# MGB-001-IO.net
KiCad netlist of a schematic drawn in EAGLE
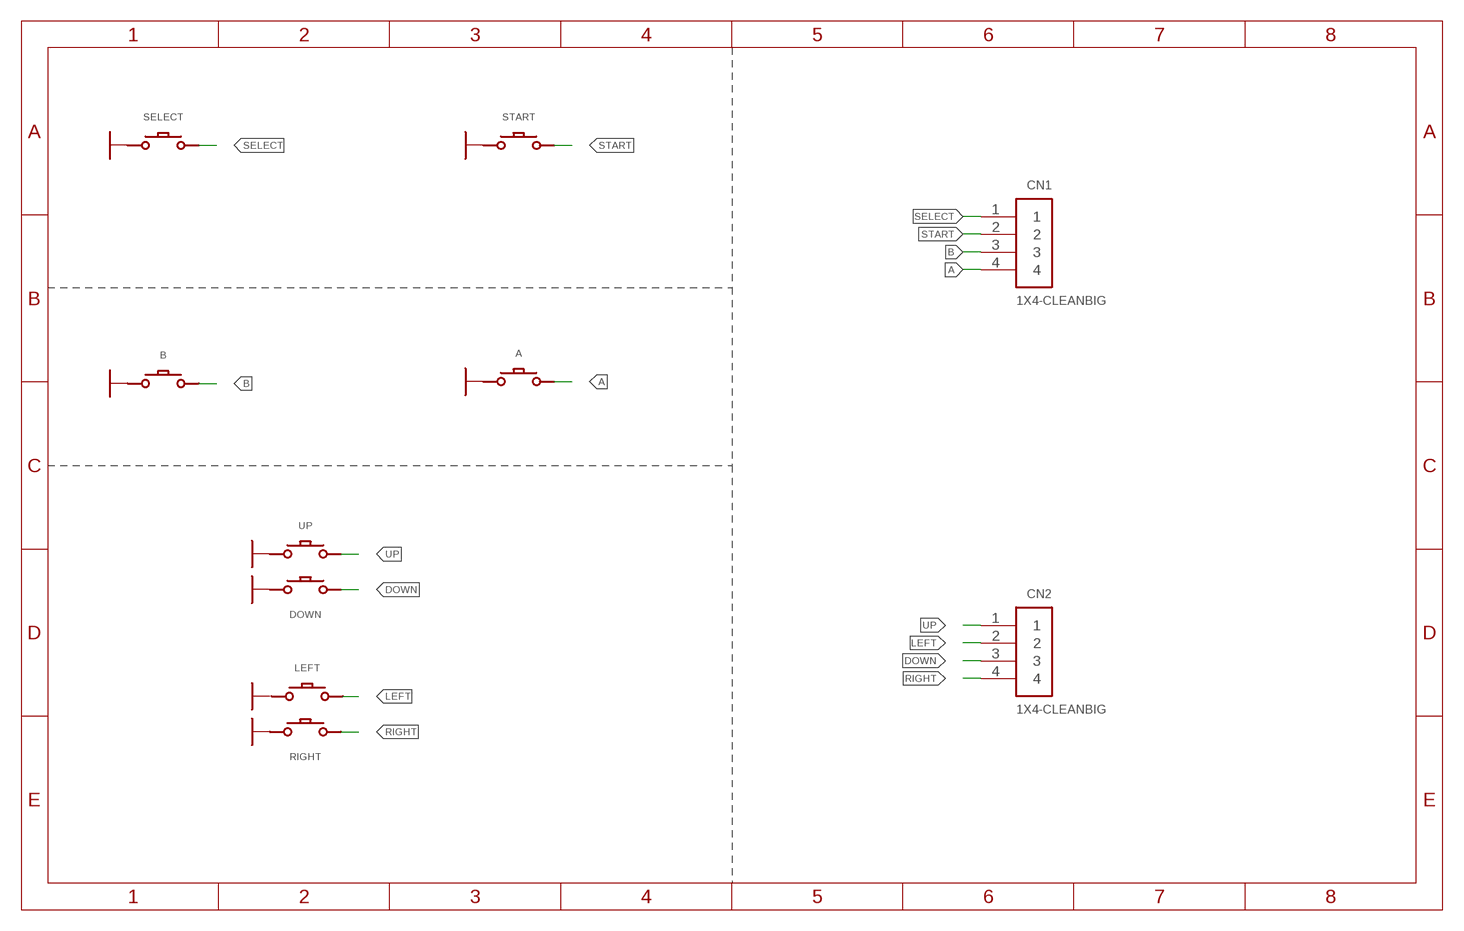
[diagram p0: schematic, sheet 1]
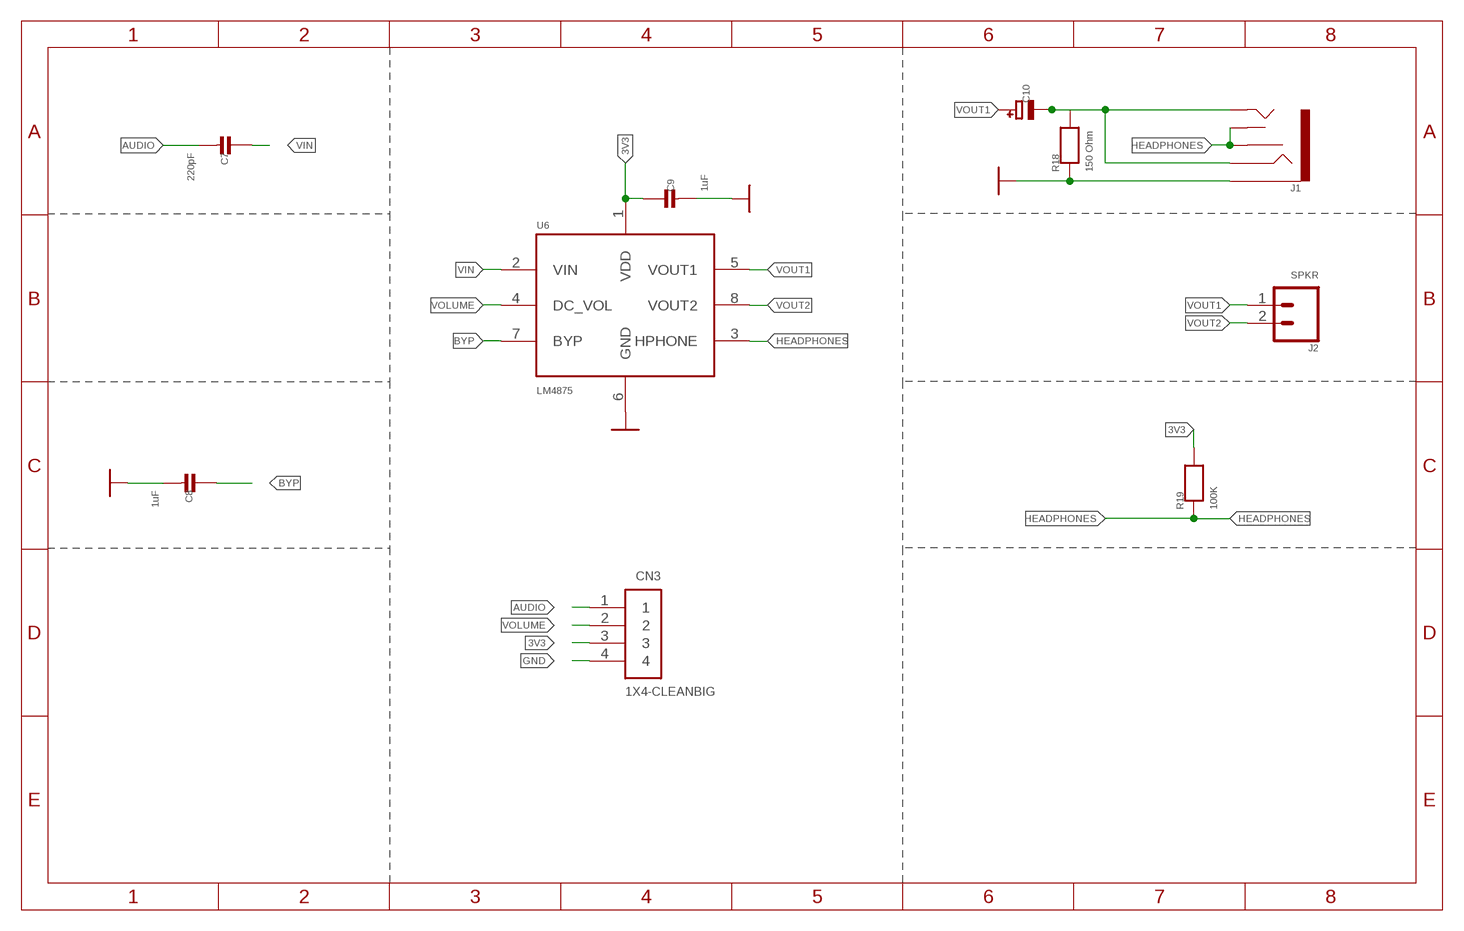
[diagram p1: schematic, sheet 2]
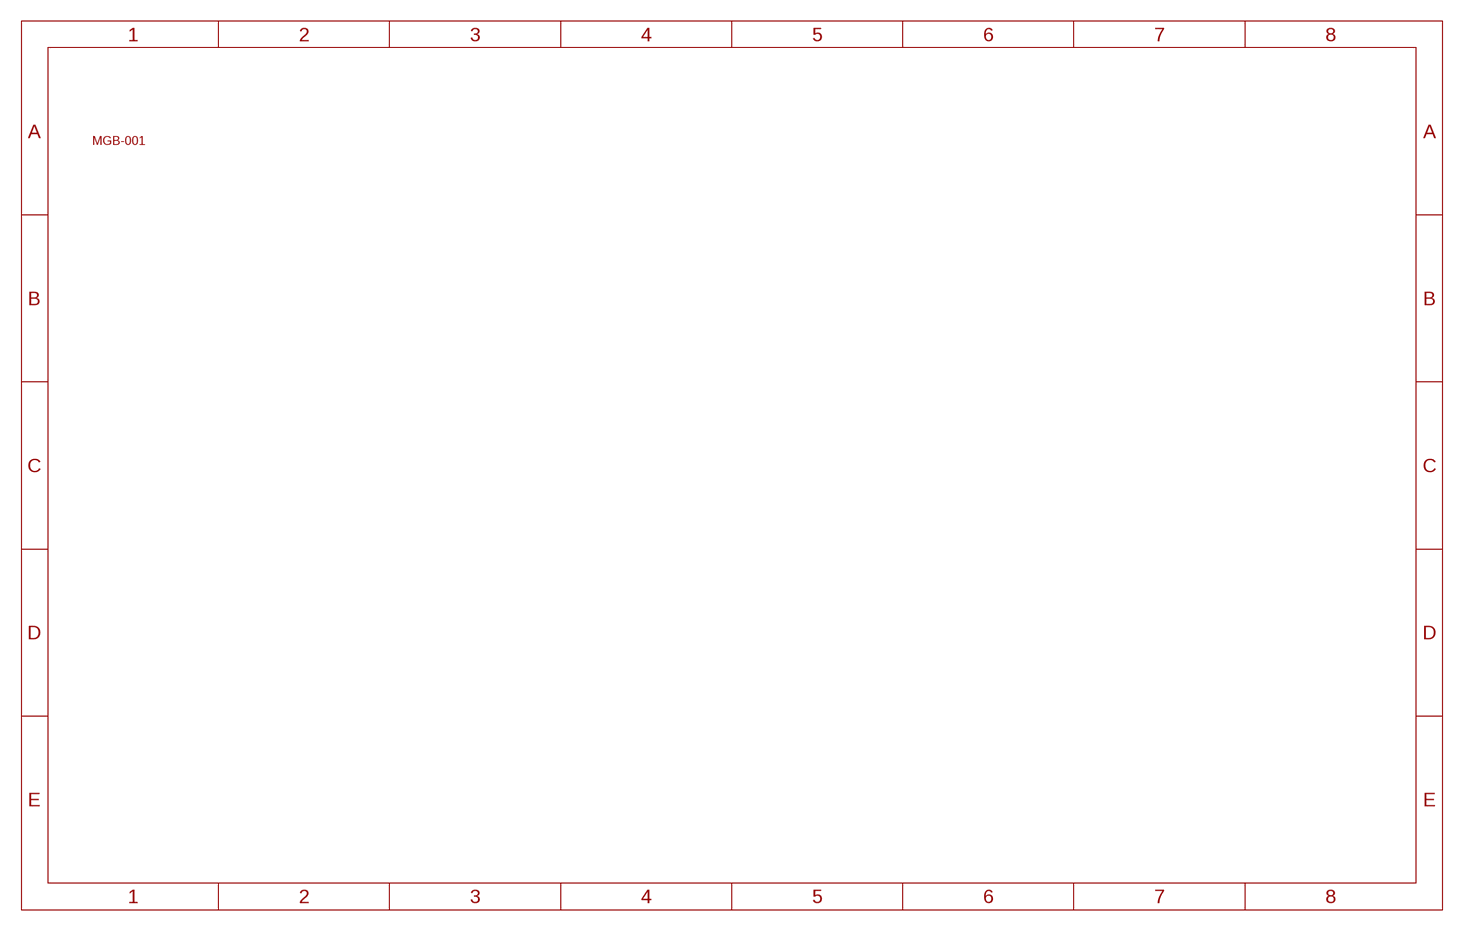
[diagram p2: schematic, sheet 3]

(export (version "E")
  (design (tool "Eeschema 10.0.6"))
  (components
    (comp (ref "C7")
      (value "220pF")
      (footprint "eagle-import:0603-MINI-CAP")
      (fields (field (name "MPN") "CL10C221JB8NNNC"))
      (libsource (lib "eagle-import") (part "CAP_CERAMIC"))
    )
    (comp (ref "C8")
      (value "1uF")
      (footprint "eagle-import:0603-MINI-CAP")
      (fields (field (name "MPN") "CL10A105KP8NNNC"))
      (libsource (lib "eagle-import") (part "CAP_CERAMIC"))
    )
    (comp (ref "C9")
      (value "1uF")
      (footprint "eagle-import:0603-MINI-CAP")
      (fields (field (name "MPN") "CL10A105KP8NNNC"))
      (libsource (lib "eagle-import") (part "CAP_CERAMIC"))
    )
    (comp (ref "C10")
      (value "100uF")
      (footprint "eagle-import:EIA3216-18_A-W")
      (fields (field (name "MPN") "F930J107KAA"))
      (libsource (lib "eagle-import") (part "CAP_TANTALUMA/3216_WAVE"))
    )
    (comp (ref "CN3")
      (value "1X4-CLEANBIG")
      (footprint "eagle-import:1X04-CLEANBIG")
      (libsource (lib "eagle-import") (part "1X4-CLEANBIG"))
    )
    (comp (ref "J1")
      (value "AUDIO_JACK_3.5MM_KIT")
      (footprint "eagle-import:AUDIO-JACK-KIT")
      (fields (field (name "MPN") "SJ1-3525NG-GR"))
      (libsource (lib "eagle-import") (part "AUDIO_JACK_3.5MM_KIT"))
    )
    (comp (ref "J2")
      (value "SPKR")
      (footprint "eagle-import:1X02")
      (libsource (lib "eagle-import") (part "CONN_02"))
    )
    (comp (ref "R18")
      (value "150 Ohm")
      (footprint "eagle-import:0603-MINI")
      (fields (field (name "MPN") "ERJ-PA3J151V"))
      (libsource (lib "eagle-import") (part "RESISTOR0603MINI"))
    )
    (comp (ref "R19")
      (value "100K")
      (footprint "eagle-import:0603-MINI")
      (fields (field (name "MPN") "ERJ-PA3J104V"))
      (libsource (lib "eagle-import") (part "RESISTOR0603MINI"))
    )
    (comp (ref "U6")
      (value "LM4875")
      (footprint "eagle-import:SOIC8")
      (fields (field (name "MPN") "LM4875MX/NOPB"))
      (libsource (lib "eagle-import") (part "LM4875"))
    )
    (comp (ref "A")
      (value "CONDUCTIVE_BUTTONCONDUCTIVE_BUTTON_THICK")
      (footprint "eagle-import:CONDUCTIVE_BUTTON_THICK")
      (libsource (lib "eagle-import") (part "CONDUCTIVE_BUTTONCONDUCTIVE_BUTTON_THICK"))
    )
    (comp (ref "B")
      (value "CONDUCTIVE_BUTTONCONDUCTIVE_BUTTON_THICK")
      (footprint "eagle-import:CONDUCTIVE_BUTTON_THICK")
      (libsource (lib "eagle-import") (part "CONDUCTIVE_BUTTONCONDUCTIVE_BUTTON_THICK"))
    )
    (comp (ref "CN1")
      (value "1X4-CLEANBIG")
      (footprint "eagle-import:1X04-CLEANBIG")
      (libsource (lib "eagle-import") (part "1X4-CLEANBIG"))
    )
    (comp (ref "CN2")
      (value "1X4-CLEANBIG")
      (footprint "eagle-import:1X04-CLEANBIG")
      (libsource (lib "eagle-import") (part "1X4-CLEANBIG"))
    )
    (comp (ref "DOWN")
      (value "CONDUCTIVE_BUTTONCONDUCTIVE_BUTTON_DIRECTIONAL_THICK")
      (footprint "eagle-import:CONDUCTIVE_BUTTON_DIRECTIONAL_THICK")
      (libsource (lib "eagle-import") (part "CONDUCTIVE_BUTTONCONDUCTIVE_BUTTON_DIRECTIONAL_THICK"))
    )
    (comp (ref "LEFT")
      (value "CONDUCTIVE_BUTTONCONDUCTIVE_BUTTON_DIRECTIONAL_THICK")
      (footprint "eagle-import:CONDUCTIVE_BUTTON_DIRECTIONAL_THICK")
      (libsource (lib "eagle-import") (part "CONDUCTIVE_BUTTONCONDUCTIVE_BUTTON_DIRECTIONAL_THICK"))
    )
    (comp (ref "RIGHT")
      (value "CONDUCTIVE_BUTTONCONDUCTIVE_BUTTON_DIRECTIONAL_THICK")
      (footprint "eagle-import:CONDUCTIVE_BUTTON_DIRECTIONAL_THICK")
      (libsource (lib "eagle-import") (part "CONDUCTIVE_BUTTONCONDUCTIVE_BUTTON_DIRECTIONAL_THICK"))
    )
    (comp (ref "SELECT")
      (value "CONDUCTIVE_BUTTON_STARTSELECTCONDUCTIVE_BUTTON_THICK_STARTSELECT")
      (footprint "eagle-import:CONDUCTIVE_BUTTON_THICK_STARTSELECT")
      (libsource (lib "eagle-import") (part "CONDUCTIVE_BUTTON_STARTSELECTCONDUCTIVE_BUTTON_THICK_STARTSELECT"))
    )
    (comp (ref "START")
      (value "CONDUCTIVE_BUTTON_STARTSELECTCONDUCTIVE_BUTTON_THICK_STARTSELECT")
      (footprint "eagle-import:CONDUCTIVE_BUTTON_THICK_STARTSELECT")
      (libsource (lib "eagle-import") (part "CONDUCTIVE_BUTTON_STARTSELECTCONDUCTIVE_BUTTON_THICK_STARTSELECT"))
    )
    (comp (ref "UP")
      (value "CONDUCTIVE_BUTTONCONDUCTIVE_BUTTON_DIRECTIONAL_THICK")
      (footprint "eagle-import:CONDUCTIVE_BUTTON_DIRECTIONAL_THICK")
      (libsource (lib "eagle-import") (part "CONDUCTIVE_BUTTONCONDUCTIVE_BUTTON_DIRECTIONAL_THICK"))
    )
    (comp (ref "U$17")
      (value "MGB-001MGB-001-IO")
      (footprint "eagle-import:MGB-001-IO")
      (libsource (lib "eagle-import") (part "MGB-001MGB-001-IO"))
    )
  )
  (nets
    (net (code "1") (name "3V3") (class "Default")
      (node (ref "C9") (pin "1") (pinfunction "1_1") (pintype "passive"))
      (node (ref "CN3") (pin "3") (pinfunction "3_3") (pintype "bidirectional"))
      (node (ref "R19") (pin "2") (pinfunction "2_2") (pintype "passive"))
      (node (ref "U6") (pin "1") (pinfunction "VDD_1") (pintype "power_in"))
    )
    (net (code "2") (name "A") (class "Default")
      (node (ref "A") (pin "P$ACTIVE") (pinfunction "P$ACTIVE_P$ACTIVE") (pintype "bidirectional"))
      (node (ref "CN1") (pin "4") (pinfunction "4_4") (pintype "bidirectional"))
    )
    (net (code "3") (name "AUDIO") (class "Default")
      (node (ref "C7") (pin "2") (pinfunction "2_2") (pintype "passive"))
      (node (ref "CN3") (pin "1") (pinfunction "1_1") (pintype "bidirectional"))
    )
    (net (code "4") (name "B") (class "Default")
      (node (ref "B") (pin "P$ACTIVE") (pinfunction "P$ACTIVE_P$ACTIVE") (pintype "bidirectional"))
      (node (ref "CN1") (pin "3") (pinfunction "3_3") (pintype "bidirectional"))
    )
    (net (code "5") (name "BYP") (class "Default")
      (node (ref "C8") (pin "1") (pinfunction "1_1") (pintype "passive"))
      (node (ref "U6") (pin "7") (pinfunction "BYP_7") (pintype "bidirectional"))
    )
    (net (code "6") (name "DOWN") (class "Default")
      (node (ref "CN2") (pin "3") (pinfunction "3_3") (pintype "bidirectional"))
      (node (ref "DOWN") (pin "P$ACTIVE") (pinfunction "P$ACTIVE_P$ACTIVE") (pintype "bidirectional"))
    )
    (net (code "7") (name "GND") (class "Default")
      (node (ref "A") (pin "P$GND") (pinfunction "P$GND_P$GND") (pintype "bidirectional"))
      (node (ref "B") (pin "P$GND") (pinfunction "P$GND_P$GND") (pintype "bidirectional"))
      (node (ref "C8") (pin "2") (pinfunction "2_2") (pintype "passive"))
      (node (ref "C9") (pin "2") (pinfunction "2_2") (pintype "passive"))
      (node (ref "CN3") (pin "4") (pinfunction "4_4") (pintype "bidirectional"))
      (node (ref "DOWN") (pin "P$GND") (pinfunction "P$GND_P$GND") (pintype "bidirectional"))
      (node (ref "J1") (pin "SLEEVE") (pinfunction "SLEEVE_SLEEVE") (pintype "bidirectional"))
      (node (ref "R18") (pin "1") (pinfunction "1_1") (pintype "passive"))
      (node (ref "RIGHT") (pin "P$GND") (pinfunction "P$GND_P$GND") (pintype "bidirectional"))
      (node (ref "SELECT") (pin "P$GND") (pinfunction "P$GND_P$GND") (pintype "bidirectional"))
      (node (ref "SELECT") (pin "P$GND1") (pinfunction "P$GND_P$GND1") (pintype "bidirectional"))
      (node (ref "SELECT") (pin "P$GND2") (pinfunction "P$GND_P$GND2") (pintype "bidirectional"))
      (node (ref "SELECT") (pin "P$GND3") (pinfunction "P$GND_P$GND3") (pintype "bidirectional"))
      (node (ref "START") (pin "P$GND") (pinfunction "P$GND_P$GND") (pintype "bidirectional"))
      (node (ref "START") (pin "P$GND1") (pinfunction "P$GND_P$GND1") (pintype "bidirectional"))
      (node (ref "START") (pin "P$GND2") (pinfunction "P$GND_P$GND2") (pintype "bidirectional"))
      (node (ref "START") (pin "P$GND3") (pinfunction "P$GND_P$GND3") (pintype "bidirectional"))
      (node (ref "U6") (pin "6") (pinfunction "GND_6") (pintype "power_in"))
      (node (ref "UP") (pin "P$GND") (pinfunction "P$GND_P$GND") (pintype "bidirectional"))
    )
    (net (code "8") (name "HEADPHONES") (class "Default")
      (node (ref "J1") (pin "RSH") (pinfunction "RSH_RSH") (pintype "bidirectional"))
      (node (ref "J1") (pin "TSH") (pinfunction "TSH_TSH") (pintype "bidirectional"))
      (node (ref "R19") (pin "1") (pinfunction "1_1") (pintype "passive"))
      (node (ref "U6") (pin "3") (pinfunction "HPHONE_3") (pintype "input"))
    )
    (net (code "9") (name "LEFT") (class "Default")
      (node (ref "CN2") (pin "2") (pinfunction "2_2") (pintype "bidirectional"))
      (node (ref "LEFT") (pin "P$ACTIVE") (pinfunction "P$ACTIVE_P$ACTIVE") (pintype "bidirectional"))
    )
    (net (code "10") (name "Net-(C10-Pad-)") (class "Default")
      (node (ref "C10") (pin "-") (pinfunction "-_-") (pintype "passive"))
      (node (ref "J1") (pin "RING") (pinfunction "RING_RING") (pintype "bidirectional"))
      (node (ref "J1") (pin "TIP") (pinfunction "TIP_TIP") (pintype "bidirectional"))
      (node (ref "R18") (pin "2") (pinfunction "2_2") (pintype "passive"))
    )
    (net (code "11") (name "RIGHT") (class "Default")
      (node (ref "CN2") (pin "4") (pinfunction "4_4") (pintype "bidirectional"))
      (node (ref "RIGHT") (pin "P$ACTIVE") (pinfunction "P$ACTIVE_P$ACTIVE") (pintype "bidirectional"))
    )
    (net (code "12") (name "SELECT") (class "Default")
      (node (ref "CN1") (pin "1") (pinfunction "1_1") (pintype "bidirectional"))
      (node (ref "SELECT") (pin "P$ACTIVE") (pinfunction "P$ACTIVE_P$ACTIVE") (pintype "bidirectional"))
      (node (ref "SELECT") (pin "P$ACTIVE1") (pinfunction "P$ACTIVE_P$ACTIVE1") (pintype "bidirectional"))
      (node (ref "SELECT") (pin "P$ACTIVE2") (pinfunction "P$ACTIVE_P$ACTIVE2") (pintype "bidirectional"))
      (node (ref "SELECT") (pin "P$ACTIVE3") (pinfunction "P$ACTIVE_P$ACTIVE3") (pintype "bidirectional"))
      (node (ref "SELECT") (pin "P$ACTIVE4") (pinfunction "P$ACTIVE_P$ACTIVE4") (pintype "bidirectional"))
      (node (ref "SELECT") (pin "P$ACTIVE5") (pinfunction "P$ACTIVE_P$ACTIVE5") (pintype "bidirectional"))
      (node (ref "SELECT") (pin "P$ACTIVE6") (pinfunction "P$ACTIVE_P$ACTIVE6") (pintype "bidirectional"))
    )
    (net (code "13") (name "START") (class "Default")
      (node (ref "CN1") (pin "2") (pinfunction "2_2") (pintype "bidirectional"))
      (node (ref "START") (pin "P$ACTIVE") (pinfunction "P$ACTIVE_P$ACTIVE") (pintype "bidirectional"))
      (node (ref "START") (pin "P$ACTIVE1") (pinfunction "P$ACTIVE_P$ACTIVE1") (pintype "bidirectional"))
      (node (ref "START") (pin "P$ACTIVE2") (pinfunction "P$ACTIVE_P$ACTIVE2") (pintype "bidirectional"))
      (node (ref "START") (pin "P$ACTIVE3") (pinfunction "P$ACTIVE_P$ACTIVE3") (pintype "bidirectional"))
      (node (ref "START") (pin "P$ACTIVE4") (pinfunction "P$ACTIVE_P$ACTIVE4") (pintype "bidirectional"))
      (node (ref "START") (pin "P$ACTIVE5") (pinfunction "P$ACTIVE_P$ACTIVE5") (pintype "bidirectional"))
      (node (ref "START") (pin "P$ACTIVE6") (pinfunction "P$ACTIVE_P$ACTIVE6") (pintype "bidirectional"))
    )
    (net (code "14") (name "UP") (class "Default")
      (node (ref "CN2") (pin "1") (pinfunction "1_1") (pintype "bidirectional"))
      (node (ref "UP") (pin "P$ACTIVE") (pinfunction "P$ACTIVE_P$ACTIVE") (pintype "bidirectional"))
    )
    (net (code "15") (name "VIN") (class "Default")
      (node (ref "C7") (pin "1") (pinfunction "1_1") (pintype "passive"))
      (node (ref "U6") (pin "2") (pinfunction "VIN_2") (pintype "input"))
    )
    (net (code "16") (name "VOLUME") (class "Default")
      (node (ref "CN3") (pin "2") (pinfunction "2_2") (pintype "bidirectional"))
      (node (ref "U6") (pin "4") (pinfunction "DC_VOL_4") (pintype "input"))
    )
    (net (code "17") (name "VOUT1") (class "Default")
      (node (ref "C10") (pin "+") (pinfunction "+_+") (pintype "passive"))
      (node (ref "J2") (pin "1") (pinfunction "1_1") (pintype "passive"))
      (node (ref "U6") (pin "5") (pinfunction "VOUT1_5") (pintype "output"))
    )
    (net (code "18") (name "VOUT2") (class "Default")
      (node (ref "J2") (pin "2") (pinfunction "2_2") (pintype "passive"))
      (node (ref "U6") (pin "8") (pinfunction "VOUT2_8") (pintype "output"))
    )
    (net (code "19") (name "unconnected-(LEFT-PadP$GND)") (class "Default")
      (node (ref "LEFT") (pin "P$GND") (pinfunction "P$GND_P$GND") (pintype "bidirectional"))
    )
  )
)
